# fakugesi_pass.net
KiCad netlist of a schematic drawn in EAGLE
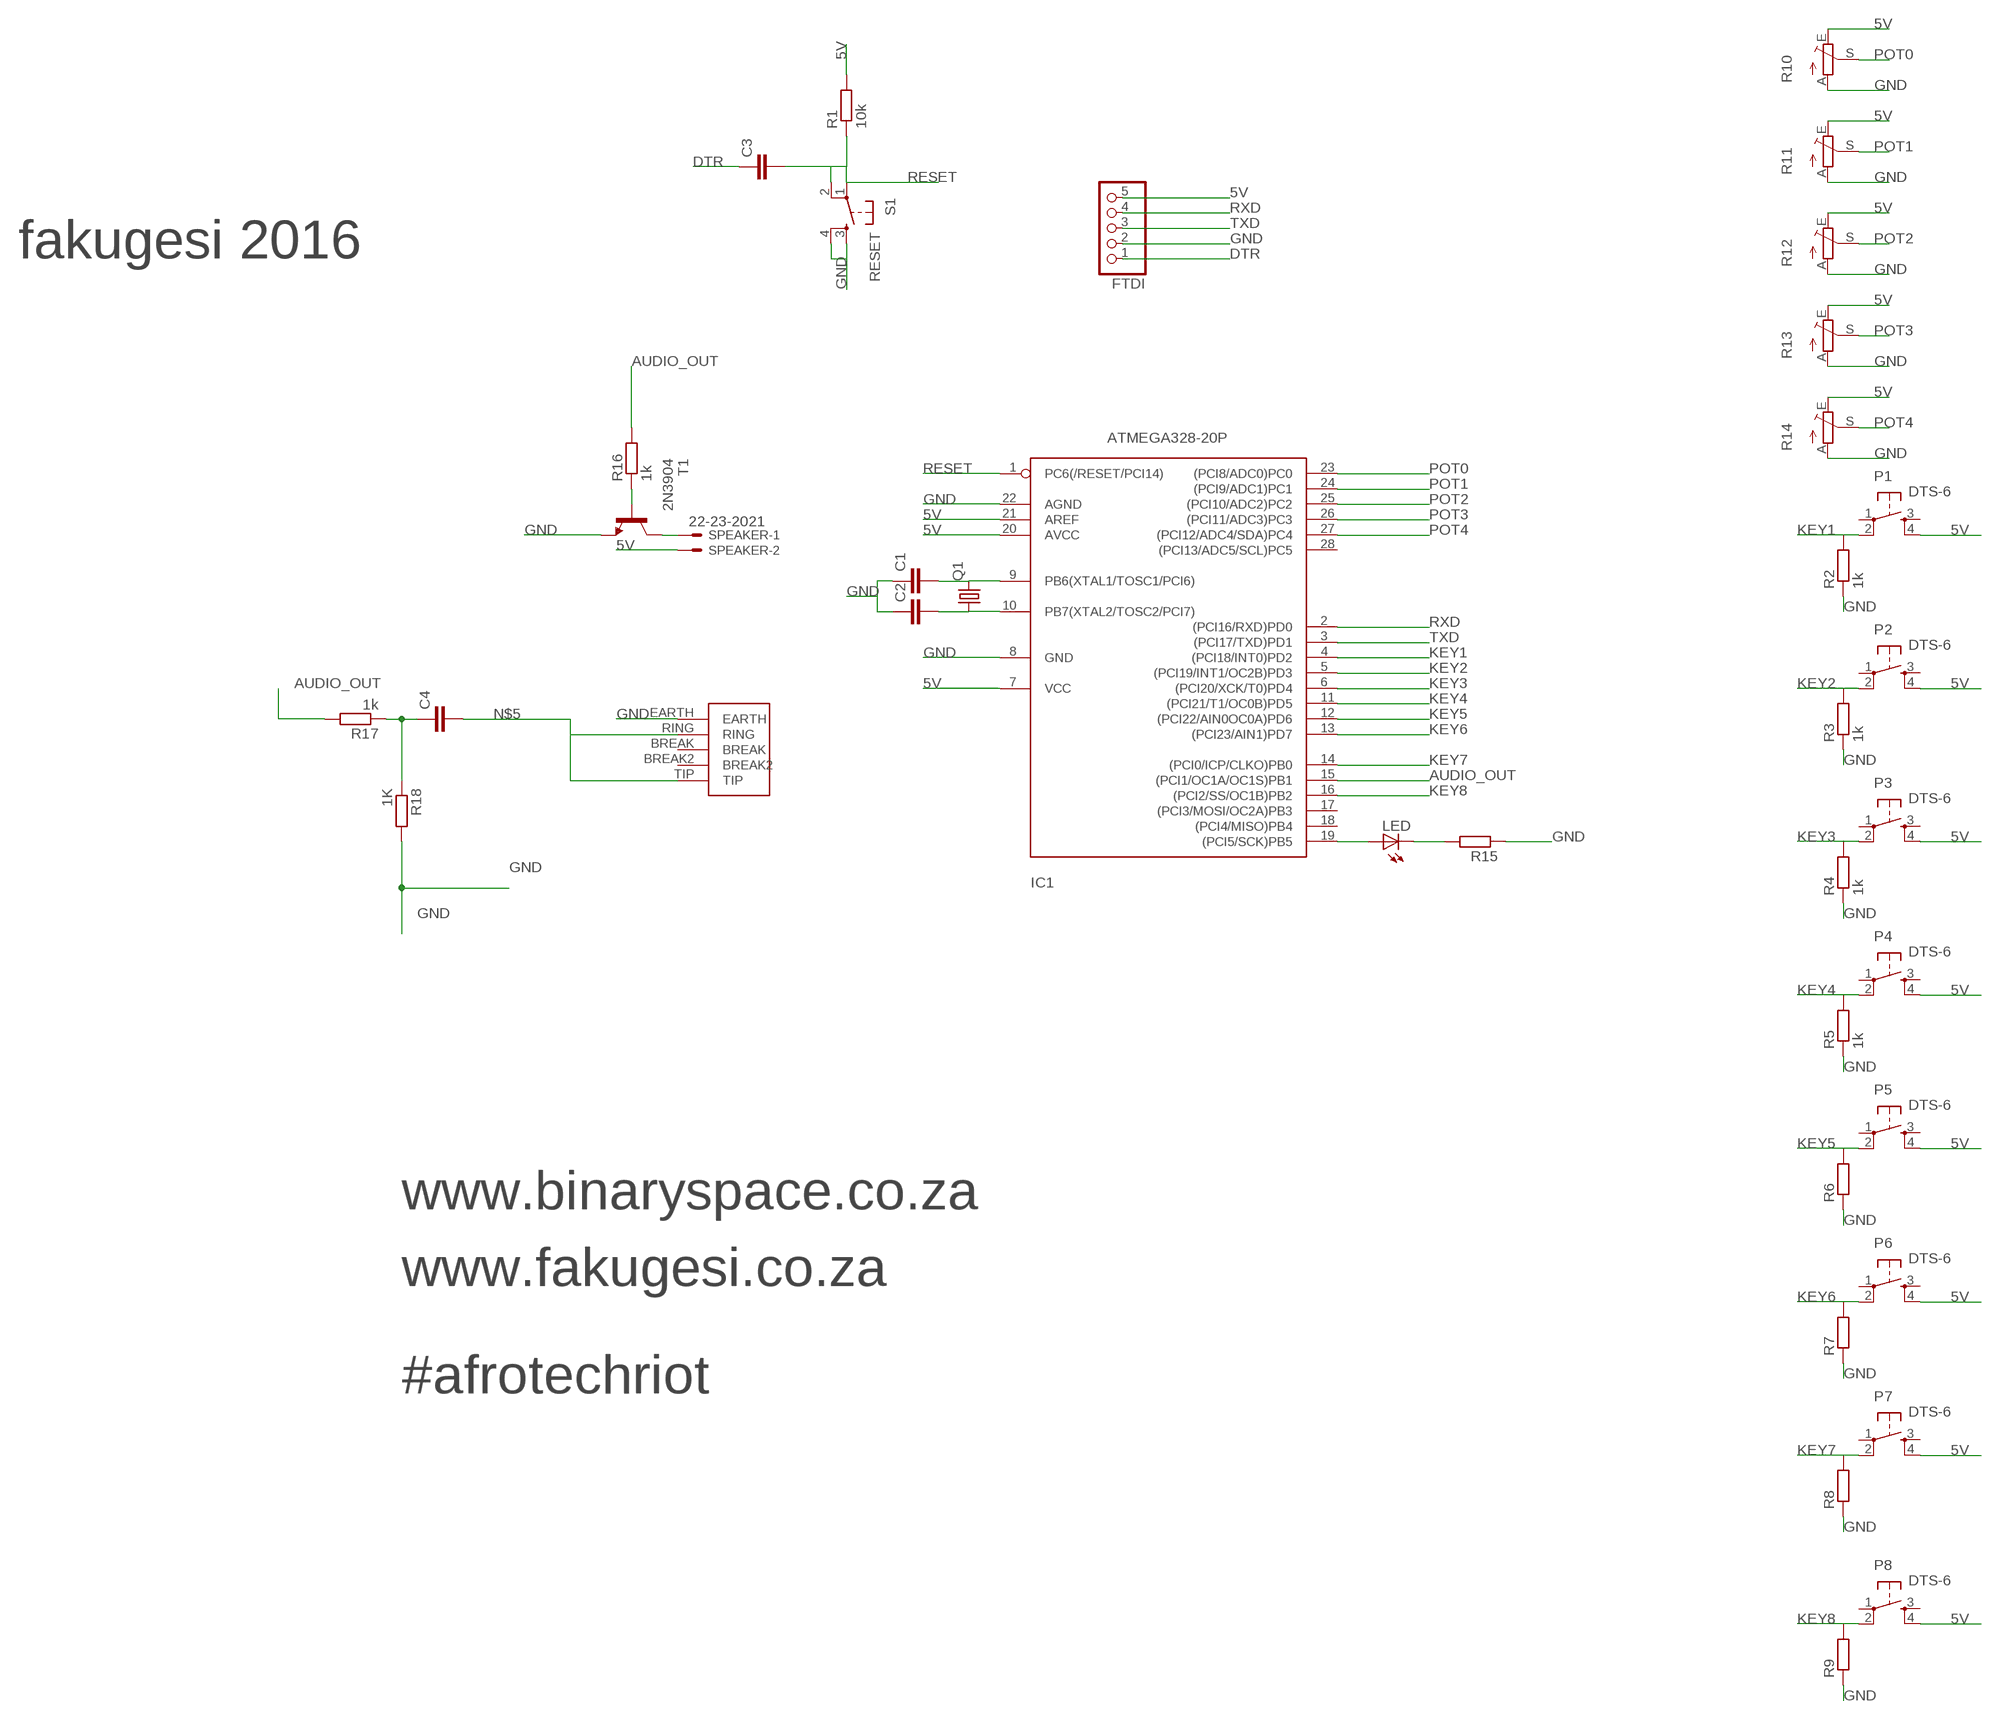
[diagram p0: schematic, sheet 1]

(export (version "E")
  (design (tool "Eeschema 10.0.6"))
  (components
    (comp (ref "C1")
      (value "C2.5/5")
      (footprint "eagle-import:C2.5-5")
      (libsource (lib "eagle-import") (part "C2.5/5"))
    )
    (comp (ref "C2")
      (value "C2.5/5")
      (footprint "eagle-import:C2.5-5")
      (libsource (lib "eagle-import") (part "C2.5/5"))
    )
    (comp (ref "C3")
      (value "C2.5/5")
      (footprint "eagle-import:C2.5-5")
      (libsource (lib "eagle-import") (part "C2.5/5"))
    )
    (comp (ref "C4")
      (value "C2.5/5")
      (footprint "eagle-import:C2.5-5")
      (libsource (lib "eagle-import") (part "C2.5/5"))
    )
    (comp (ref "FTDI")
      (value "HEADER-1X5")
      (footprint "eagle-import:1X05_OVAL")
      (libsource (lib "eagle-import") (part "HEADER-1X5"))
    )
    (comp (ref "IC1")
      (value "ATMEGA328-20P")
      (footprint "eagle-import:DIL28-3")
      (libsource (lib "eagle-import") (part "ATMEGA328P-20"))
    )
    (comp (ref "LED")
      (value "LED3MM")
      (footprint "eagle-import:LED3MM")
      (libsource (lib "eagle-import") (part "LED3MM"))
    )
    (comp (ref "P1")
      (value "DTS-6")
      (footprint "eagle-import:DTS-6")
      (libsource (lib "eagle-import") (part "DTS-6"))
    )
    (comp (ref "P2")
      (value "DTS-6")
      (footprint "eagle-import:DTS-6")
      (libsource (lib "eagle-import") (part "DTS-6"))
    )
    (comp (ref "P3")
      (value "DTS-6")
      (footprint "eagle-import:DTS-6")
      (libsource (lib "eagle-import") (part "DTS-6"))
    )
    (comp (ref "P4")
      (value "DTS-6")
      (footprint "eagle-import:DTS-6")
      (libsource (lib "eagle-import") (part "DTS-6"))
    )
    (comp (ref "P5")
      (value "DTS-6")
      (footprint "eagle-import:DTS-6")
      (libsource (lib "eagle-import") (part "DTS-6"))
    )
    (comp (ref "P6")
      (value "DTS-6")
      (footprint "eagle-import:DTS-6")
      (libsource (lib "eagle-import") (part "DTS-6"))
    )
    (comp (ref "P7")
      (value "DTS-6")
      (footprint "eagle-import:DTS-6")
      (libsource (lib "eagle-import") (part "DTS-6"))
    )
    (comp (ref "P8")
      (value "DTS-6")
      (footprint "eagle-import:DTS-6")
      (libsource (lib "eagle-import") (part "DTS-6"))
    )
    (comp (ref "Q1")
      (value "CRYTALHC49S")
      (footprint "eagle-import:HC49_S")
      (libsource (lib "eagle-import") (part "CRYTALHC49S"))
    )
    (comp (ref "R1")
      (value "10k")
      (footprint "eagle-import:0207_7")
      (libsource (lib "eagle-import") (part "resistor_R-EU_0207/7"))
    )
    (comp (ref "R2")
      (value "1k")
      (footprint "eagle-import:0207_7")
      (libsource (lib "eagle-import") (part "resistor_R-EU_0207/7"))
    )
    (comp (ref "R3")
      (value "1k")
      (footprint "eagle-import:0207_7")
      (libsource (lib "eagle-import") (part "resistor_R-EU_0207/7"))
    )
    (comp (ref "R4")
      (value "1k")
      (footprint "eagle-import:0207_7")
      (libsource (lib "eagle-import") (part "resistor_R-EU_0207/7"))
    )
    (comp (ref "R5")
      (value "1k")
      (footprint "eagle-import:0207_7")
      (libsource (lib "eagle-import") (part "resistor_R-EU_0207/7"))
    )
    (comp (ref "R6")
      (value "R-EU_0207/7")
      (footprint "eagle-import:0207_7")
      (libsource (lib "eagle-import") (part "resistor_R-EU_0207/7"))
    )
    (comp (ref "R7")
      (value "R-EU_0207/7")
      (footprint "eagle-import:0207_7")
      (libsource (lib "eagle-import") (part "resistor_R-EU_0207/7"))
    )
    (comp (ref "R8")
      (value "R-EU_0207/7")
      (footprint "eagle-import:0207_7")
      (libsource (lib "eagle-import") (part "resistor_R-EU_0207/7"))
    )
    (comp (ref "R9")
      (value "R-EU_0207/7")
      (footprint "eagle-import:0207_7")
      (libsource (lib "eagle-import") (part "resistor_R-EU_0207/7"))
    )
    (comp (ref "R10")
      (value "TRIM_EU-RS3")
      (footprint "eagle-import:RS3")
      (libsource (lib "eagle-import") (part "TRIM_EU-RS3"))
    )
    (comp (ref "R11")
      (value "TRIM_EU-RS3")
      (footprint "eagle-import:RS3")
      (libsource (lib "eagle-import") (part "TRIM_EU-RS3"))
    )
    (comp (ref "R12")
      (value "TRIM_EU-RS3")
      (footprint "eagle-import:RS3")
      (libsource (lib "eagle-import") (part "TRIM_EU-RS3"))
    )
    (comp (ref "R13")
      (value "TRIM_EU-RS3")
      (footprint "eagle-import:RS3")
      (libsource (lib "eagle-import") (part "TRIM_EU-RS3"))
    )
    (comp (ref "R14")
      (value "TRIM_EU-RS3")
      (footprint "eagle-import:RS3")
      (libsource (lib "eagle-import") (part "TRIM_EU-RS3"))
    )
    (comp (ref "R15")
      (value "R-EU_0207/7")
      (footprint "eagle-import:0207_7")
      (libsource (lib "eagle-import") (part "R-EU_0207/7"))
    )
    (comp (ref "R16")
      (value "1k")
      (footprint "eagle-import:0207_7")
      (libsource (lib "eagle-import") (part "resistor_R-EU_0207/7"))
    )
    (comp (ref "R17")
      (value "1k")
      (footprint "eagle-import:0207_7")
      (libsource (lib "eagle-import") (part "resistor_R-EU_0207/7"))
    )
    (comp (ref "R18")
      (value "1K")
      (footprint "eagle-import:0207_7")
      (libsource (lib "eagle-import") (part "resistor_R-EU_0207/7"))
    )
    (comp (ref "S1")
      (value "RESET")
      (footprint "eagle-import:DTS-6")
      (libsource (lib "eagle-import") (part "DTS-6"))
    )
    (comp (ref "SPEAKER")
      (value "22-23-2021")
      (footprint "eagle-import:22-23-2021")
      (fields (field (name "MF") "MOLEX"))
      (libsource (lib "eagle-import") (part "22-23-2021"))
    )
    (comp (ref "T1")
      (value "2N3904")
      (footprint "eagle-import:TO92")
      (libsource (lib "eagle-import") (part "2N3904"))
    )
    (comp (ref "U$1")
      (value "3.5MMAUDIOJACKPCB")
      (footprint "eagle-import:3.5MMAUDIOJACK")
      (libsource (lib "eagle-import") (part "3.5MMAUDIOJACKPCB"))
    )
  )
  (nets
    (net (code "1") (name "/5V") (class "Default")
      (node (ref "FTDI") (pin "5") (pinfunction "5_5") (pintype "passive"))
      (node (ref "IC1") (pin "20") (pinfunction "AVCC_20") (pintype "bidirectional"))
      (node (ref "IC1") (pin "21") (pinfunction "AREF_21") (pintype "bidirectional"))
      (node (ref "IC1") (pin "7") (pinfunction "VCC_7") (pintype "bidirectional"))
      (node (ref "P1") (pin "4") (pinfunction "4_4") (pintype "passive"))
      (node (ref "P2") (pin "4") (pinfunction "4_4") (pintype "passive"))
      (node (ref "P3") (pin "4") (pinfunction "4_4") (pintype "passive"))
      (node (ref "P4") (pin "4") (pinfunction "4_4") (pintype "passive"))
      (node (ref "P5") (pin "4") (pinfunction "4_4") (pintype "passive"))
      (node (ref "P6") (pin "4") (pinfunction "4_4") (pintype "passive"))
      (node (ref "P7") (pin "4") (pinfunction "4_4") (pintype "passive"))
      (node (ref "P8") (pin "4") (pinfunction "4_4") (pintype "passive"))
      (node (ref "R1") (pin "2") (pinfunction "2_2") (pintype "passive"))
      (node (ref "R10") (pin "E") (pinfunction "E_E") (pintype "passive"))
      (node (ref "R11") (pin "E") (pinfunction "E_E") (pintype "passive"))
      (node (ref "R12") (pin "E") (pinfunction "E_E") (pintype "passive"))
      (node (ref "R13") (pin "E") (pinfunction "E_E") (pintype "passive"))
      (node (ref "R14") (pin "E") (pinfunction "E_E") (pintype "passive"))
      (node (ref "SPEAKER") (pin "2") (pinfunction "S_2") (pintype "passive"))
    )
    (net (code "2") (name "/AUDIO_OUT") (class "Default")
      (node (ref "IC1") (pin "15") (pinfunction "(PCI1/OC1A/OC1S)PB1_15") (pintype "bidirectional"))
      (node (ref "R16") (pin "2") (pinfunction "2_2") (pintype "passive"))
      (node (ref "R17") (pin "2") (pinfunction "2_2") (pintype "passive"))
    )
    (net (code "3") (name "/DTR") (class "Default")
      (node (ref "C3") (pin "1") (pinfunction "1_1") (pintype "passive"))
      (node (ref "FTDI") (pin "1") (pinfunction "1_1") (pintype "passive"))
    )
    (net (code "4") (name "/GND") (class "Default")
      (node (ref "C1") (pin "1") (pinfunction "1_1") (pintype "passive"))
      (node (ref "C2") (pin "1") (pinfunction "1_1") (pintype "passive"))
      (node (ref "FTDI") (pin "2") (pinfunction "2_2") (pintype "passive"))
      (node (ref "IC1") (pin "22") (pinfunction "AGND_22") (pintype "bidirectional"))
      (node (ref "IC1") (pin "8") (pinfunction "GND_8") (pintype "bidirectional"))
      (node (ref "R10") (pin "A") (pinfunction "A_A") (pintype "passive"))
      (node (ref "R11") (pin "A") (pinfunction "A_A") (pintype "passive"))
      (node (ref "R12") (pin "A") (pinfunction "A_A") (pintype "passive"))
      (node (ref "R13") (pin "A") (pinfunction "A_A") (pintype "passive"))
      (node (ref "R14") (pin "A") (pinfunction "A_A") (pintype "passive"))
      (node (ref "R15") (pin "1") (pinfunction "1_1") (pintype "passive"))
      (node (ref "R18") (pin "2") (pinfunction "2_2") (pintype "passive"))
      (node (ref "R2") (pin "1") (pinfunction "1_1") (pintype "passive"))
      (node (ref "R3") (pin "1") (pinfunction "1_1") (pintype "passive"))
      (node (ref "R4") (pin "1") (pinfunction "1_1") (pintype "passive"))
      (node (ref "R5") (pin "1") (pinfunction "1_1") (pintype "passive"))
      (node (ref "R6") (pin "1") (pinfunction "1_1") (pintype "passive"))
      (node (ref "R7") (pin "1") (pinfunction "1_1") (pintype "passive"))
      (node (ref "R8") (pin "1") (pinfunction "1_1") (pintype "passive"))
      (node (ref "R9") (pin "1") (pinfunction "1_1") (pintype "passive"))
      (node (ref "S1") (pin "3") (pinfunction "3_3") (pintype "passive"))
      (node (ref "S1") (pin "4") (pinfunction "4_4") (pintype "passive"))
      (node (ref "T1") (pin "3") (pinfunction "E_3") (pintype "passive"))
      (node (ref "U$1") (pin "EARTH") (pinfunction "EARTH_EARTH") (pintype "bidirectional"))
    )
    (net (code "5") (name "/KEY1") (class "Default")
      (node (ref "IC1") (pin "4") (pinfunction "(PCI18/INT0)PD2_4") (pintype "bidirectional"))
      (node (ref "P1") (pin "2") (pinfunction "2_2") (pintype "passive"))
      (node (ref "R2") (pin "2") (pinfunction "2_2") (pintype "passive"))
    )
    (net (code "6") (name "/KEY2") (class "Default")
      (node (ref "IC1") (pin "5") (pinfunction "(PCI19/INT1/OC2B)PD3_5") (pintype "bidirectional"))
      (node (ref "P2") (pin "2") (pinfunction "2_2") (pintype "passive"))
      (node (ref "R3") (pin "2") (pinfunction "2_2") (pintype "passive"))
    )
    (net (code "7") (name "/KEY3") (class "Default")
      (node (ref "IC1") (pin "6") (pinfunction "(PCI20/XCK/T0)PD4_6") (pintype "bidirectional"))
      (node (ref "P3") (pin "2") (pinfunction "2_2") (pintype "passive"))
      (node (ref "R4") (pin "2") (pinfunction "2_2") (pintype "passive"))
    )
    (net (code "8") (name "/KEY4") (class "Default")
      (node (ref "IC1") (pin "11") (pinfunction "(PCI21/T1/OC0B)PD5_11") (pintype "bidirectional"))
      (node (ref "P4") (pin "2") (pinfunction "2_2") (pintype "passive"))
      (node (ref "R5") (pin "2") (pinfunction "2_2") (pintype "passive"))
    )
    (net (code "9") (name "/KEY5") (class "Default")
      (node (ref "IC1") (pin "12") (pinfunction "(PCI22/AIN0OC0A)PD6_12") (pintype "bidirectional"))
      (node (ref "P5") (pin "2") (pinfunction "2_2") (pintype "passive"))
      (node (ref "R6") (pin "2") (pinfunction "2_2") (pintype "passive"))
    )
    (net (code "10") (name "/KEY6") (class "Default")
      (node (ref "IC1") (pin "13") (pinfunction "(PCI23/AIN1)PD7_13") (pintype "bidirectional"))
      (node (ref "P6") (pin "2") (pinfunction "2_2") (pintype "passive"))
      (node (ref "R7") (pin "2") (pinfunction "2_2") (pintype "passive"))
    )
    (net (code "11") (name "/KEY7") (class "Default")
      (node (ref "IC1") (pin "14") (pinfunction "(PCI0/ICP/CLKO)PB0_14") (pintype "bidirectional"))
      (node (ref "P7") (pin "2") (pinfunction "2_2") (pintype "passive"))
      (node (ref "R8") (pin "2") (pinfunction "2_2") (pintype "passive"))
    )
    (net (code "12") (name "/KEY8") (class "Default")
      (node (ref "IC1") (pin "16") (pinfunction "(PCI2/SS/OC1B)PB2_16") (pintype "bidirectional"))
      (node (ref "P8") (pin "2") (pinfunction "2_2") (pintype "passive"))
      (node (ref "R9") (pin "2") (pinfunction "2_2") (pintype "passive"))
    )
    (net (code "13") (name "/N$5") (class "Default")
      (node (ref "C4") (pin "2") (pinfunction "2_2") (pintype "passive"))
      (node (ref "U$1") (pin "RING") (pinfunction "RING_RING") (pintype "bidirectional"))
      (node (ref "U$1") (pin "TIP") (pinfunction "TIP_TIP") (pintype "bidirectional"))
    )
    (net (code "14") (name "/POT0") (class "Default")
      (node (ref "IC1") (pin "23") (pinfunction "(PCI8/ADC0)PC0_23") (pintype "bidirectional"))
      (node (ref "R10") (pin "S") (pinfunction "S_S") (pintype "passive"))
    )
    (net (code "15") (name "/POT1") (class "Default")
      (node (ref "IC1") (pin "24") (pinfunction "(PCI9/ADC1)PC1_24") (pintype "bidirectional"))
      (node (ref "R11") (pin "S") (pinfunction "S_S") (pintype "passive"))
    )
    (net (code "16") (name "/POT2") (class "Default")
      (node (ref "IC1") (pin "25") (pinfunction "(PCI10/ADC2)PC2_25") (pintype "bidirectional"))
      (node (ref "R12") (pin "S") (pinfunction "S_S") (pintype "passive"))
    )
    (net (code "17") (name "/POT3") (class "Default")
      (node (ref "IC1") (pin "26") (pinfunction "(PCI11/ADC3)PC3_26") (pintype "bidirectional"))
      (node (ref "R13") (pin "S") (pinfunction "S_S") (pintype "passive"))
    )
    (net (code "18") (name "/POT4") (class "Default")
      (node (ref "IC1") (pin "27") (pinfunction "(PCI12/ADC4/SDA)PC4_27") (pintype "bidirectional"))
      (node (ref "R14") (pin "S") (pinfunction "S_S") (pintype "passive"))
    )
    (net (code "19") (name "/RESET") (class "Default")
      (node (ref "C3") (pin "2") (pinfunction "2_2") (pintype "passive"))
      (node (ref "IC1") (pin "1") (pinfunction "PC6(/RESET/PCI14)_1") (pintype "bidirectional"))
      (node (ref "R1") (pin "1") (pinfunction "1_1") (pintype "passive"))
      (node (ref "S1") (pin "1") (pinfunction "1_1") (pintype "passive"))
      (node (ref "S1") (pin "2") (pinfunction "2_2") (pintype "passive"))
    )
    (net (code "20") (name "/RXD") (class "Default")
      (node (ref "FTDI") (pin "4") (pinfunction "4_4") (pintype "passive"))
      (node (ref "IC1") (pin "2") (pinfunction "(PCI16/RXD)PD0_2") (pintype "bidirectional"))
    )
    (net (code "21") (name "/TXD") (class "Default")
      (node (ref "FTDI") (pin "3") (pinfunction "3_3") (pintype "passive"))
      (node (ref "IC1") (pin "3") (pinfunction "(PCI17/TXD)PD1_3") (pintype "bidirectional"))
    )
    (net (code "22") (name "Net-(C4-Pad1)") (class "Default")
      (node (ref "C4") (pin "1") (pinfunction "1_1") (pintype "passive"))
      (node (ref "R17") (pin "1") (pinfunction "1_1") (pintype "passive"))
      (node (ref "R18") (pin "1") (pinfunction "1_1") (pintype "passive"))
    )
    (net (code "23") (name "Net-(IC1-(PCI5{slash}SCK)PB5)") (class "Default")
      (node (ref "IC1") (pin "19") (pinfunction "(PCI5/SCK)PB5_19") (pintype "bidirectional"))
      (node (ref "LED") (pin "A") (pinfunction "A_A") (pintype "passive"))
    )
    (net (code "24") (name "Net-(IC1-PB6(XTAL1{slash}TOSC1{slash}PCI6))") (class "Default")
      (node (ref "C1") (pin "2") (pinfunction "2_2") (pintype "passive"))
      (node (ref "IC1") (pin "9") (pinfunction "PB6(XTAL1/TOSC1/PCI6)_9") (pintype "bidirectional"))
      (node (ref "Q1") (pin "2") (pinfunction "2_2") (pintype "passive"))
    )
    (net (code "25") (name "Net-(IC1-PB7(XTAL2{slash}TOSC2{slash}PCI7))") (class "Default")
      (node (ref "C2") (pin "2") (pinfunction "2_2") (pintype "passive"))
      (node (ref "IC1") (pin "10") (pinfunction "PB7(XTAL2/TOSC2/PCI7)_10") (pintype "bidirectional"))
      (node (ref "Q1") (pin "1") (pinfunction "1_1") (pintype "passive"))
    )
    (net (code "26") (name "Net-(LED-C)") (class "Default")
      (node (ref "LED") (pin "K") (pinfunction "C_K") (pintype "passive"))
      (node (ref "R15") (pin "2") (pinfunction "2_2") (pintype "passive"))
    )
    (net (code "27") (name "Net-(SPEAKERA-S)") (class "Default")
      (node (ref "SPEAKER") (pin "1") (pinfunction "S_1") (pintype "passive"))
      (node (ref "T1") (pin "1") (pinfunction "C_1") (pintype "passive"))
    )
    (net (code "28") (name "Net-(T1-B)") (class "Default")
      (node (ref "R16") (pin "1") (pinfunction "1_1") (pintype "passive"))
      (node (ref "T1") (pin "2") (pinfunction "B_2") (pintype "passive"))
    )
    (net (code "29") (name "unconnected-(IC1-(PCI3{slash}MOSI{slash}OC2A)PB3-Pad17)") (class "Default")
      (node (ref "IC1") (pin "17") (pinfunction "(PCI3/MOSI/OC2A)PB3_17") (pintype "bidirectional"))
    )
    (net (code "30") (name "unconnected-(IC1-(PCI4{slash}MISO)PB4-Pad18)") (class "Default")
      (node (ref "IC1") (pin "18") (pinfunction "(PCI4/MISO)PB4_18") (pintype "bidirectional"))
    )
    (net (code "31") (name "unconnected-(IC1-(PCI13{slash}ADC5{slash}SCL)PC5-Pad28)") (class "Default")
      (node (ref "IC1") (pin "28") (pinfunction "(PCI13/ADC5/SCL)PC5_28") (pintype "bidirectional"))
    )
    (net (code "32") (name "unconnected-(P1-Pad1)") (class "Default")
      (node (ref "P1") (pin "1") (pinfunction "1_1") (pintype "passive"))
    )
    (net (code "33") (name "unconnected-(P1-Pad3)") (class "Default")
      (node (ref "P1") (pin "3") (pinfunction "3_3") (pintype "passive"))
    )
    (net (code "34") (name "unconnected-(P2-Pad1)") (class "Default")
      (node (ref "P2") (pin "1") (pinfunction "1_1") (pintype "passive"))
    )
    (net (code "35") (name "unconnected-(P2-Pad3)") (class "Default")
      (node (ref "P2") (pin "3") (pinfunction "3_3") (pintype "passive"))
    )
    (net (code "36") (name "unconnected-(P3-Pad1)") (class "Default")
      (node (ref "P3") (pin "1") (pinfunction "1_1") (pintype "passive"))
    )
    (net (code "37") (name "unconnected-(P3-Pad3)") (class "Default")
      (node (ref "P3") (pin "3") (pinfunction "3_3") (pintype "passive"))
    )
    (net (code "38") (name "unconnected-(P4-Pad1)") (class "Default")
      (node (ref "P4") (pin "1") (pinfunction "1_1") (pintype "passive"))
    )
    (net (code "39") (name "unconnected-(P4-Pad3)") (class "Default")
      (node (ref "P4") (pin "3") (pinfunction "3_3") (pintype "passive"))
    )
    (net (code "40") (name "unconnected-(P5-Pad1)") (class "Default")
      (node (ref "P5") (pin "1") (pinfunction "1_1") (pintype "passive"))
    )
    (net (code "41") (name "unconnected-(P5-Pad3)") (class "Default")
      (node (ref "P5") (pin "3") (pinfunction "3_3") (pintype "passive"))
    )
    (net (code "42") (name "unconnected-(P6-Pad1)") (class "Default")
      (node (ref "P6") (pin "1") (pinfunction "1_1") (pintype "passive"))
    )
    (net (code "43") (name "unconnected-(P6-Pad3)") (class "Default")
      (node (ref "P6") (pin "3") (pinfunction "3_3") (pintype "passive"))
    )
    (net (code "44") (name "unconnected-(P7-Pad1)") (class "Default")
      (node (ref "P7") (pin "1") (pinfunction "1_1") (pintype "passive"))
    )
    (net (code "45") (name "unconnected-(P7-Pad3)") (class "Default")
      (node (ref "P7") (pin "3") (pinfunction "3_3") (pintype "passive"))
    )
    (net (code "46") (name "unconnected-(P8-Pad1)") (class "Default")
      (node (ref "P8") (pin "1") (pinfunction "1_1") (pintype "passive"))
    )
    (net (code "47") (name "unconnected-(P8-Pad3)") (class "Default")
      (node (ref "P8") (pin "3") (pinfunction "3_3") (pintype "passive"))
    )
    (net (code "48") (name "unconnected-(U$1-PadBREAK)") (class "Default")
      (node (ref "U$1") (pin "BREAK") (pinfunction "BREAK_BREAK") (pintype "bidirectional"))
    )
    (net (code "49") (name "unconnected-(U$1-PadBREAK2)") (class "Default")
      (node (ref "U$1") (pin "BREAK2") (pinfunction "BREAK2_BREAK2") (pintype "bidirectional"))
    )
  )
)
